# ComeNCap3.net
KiCad netlist of a schematic drawn in EAGLE
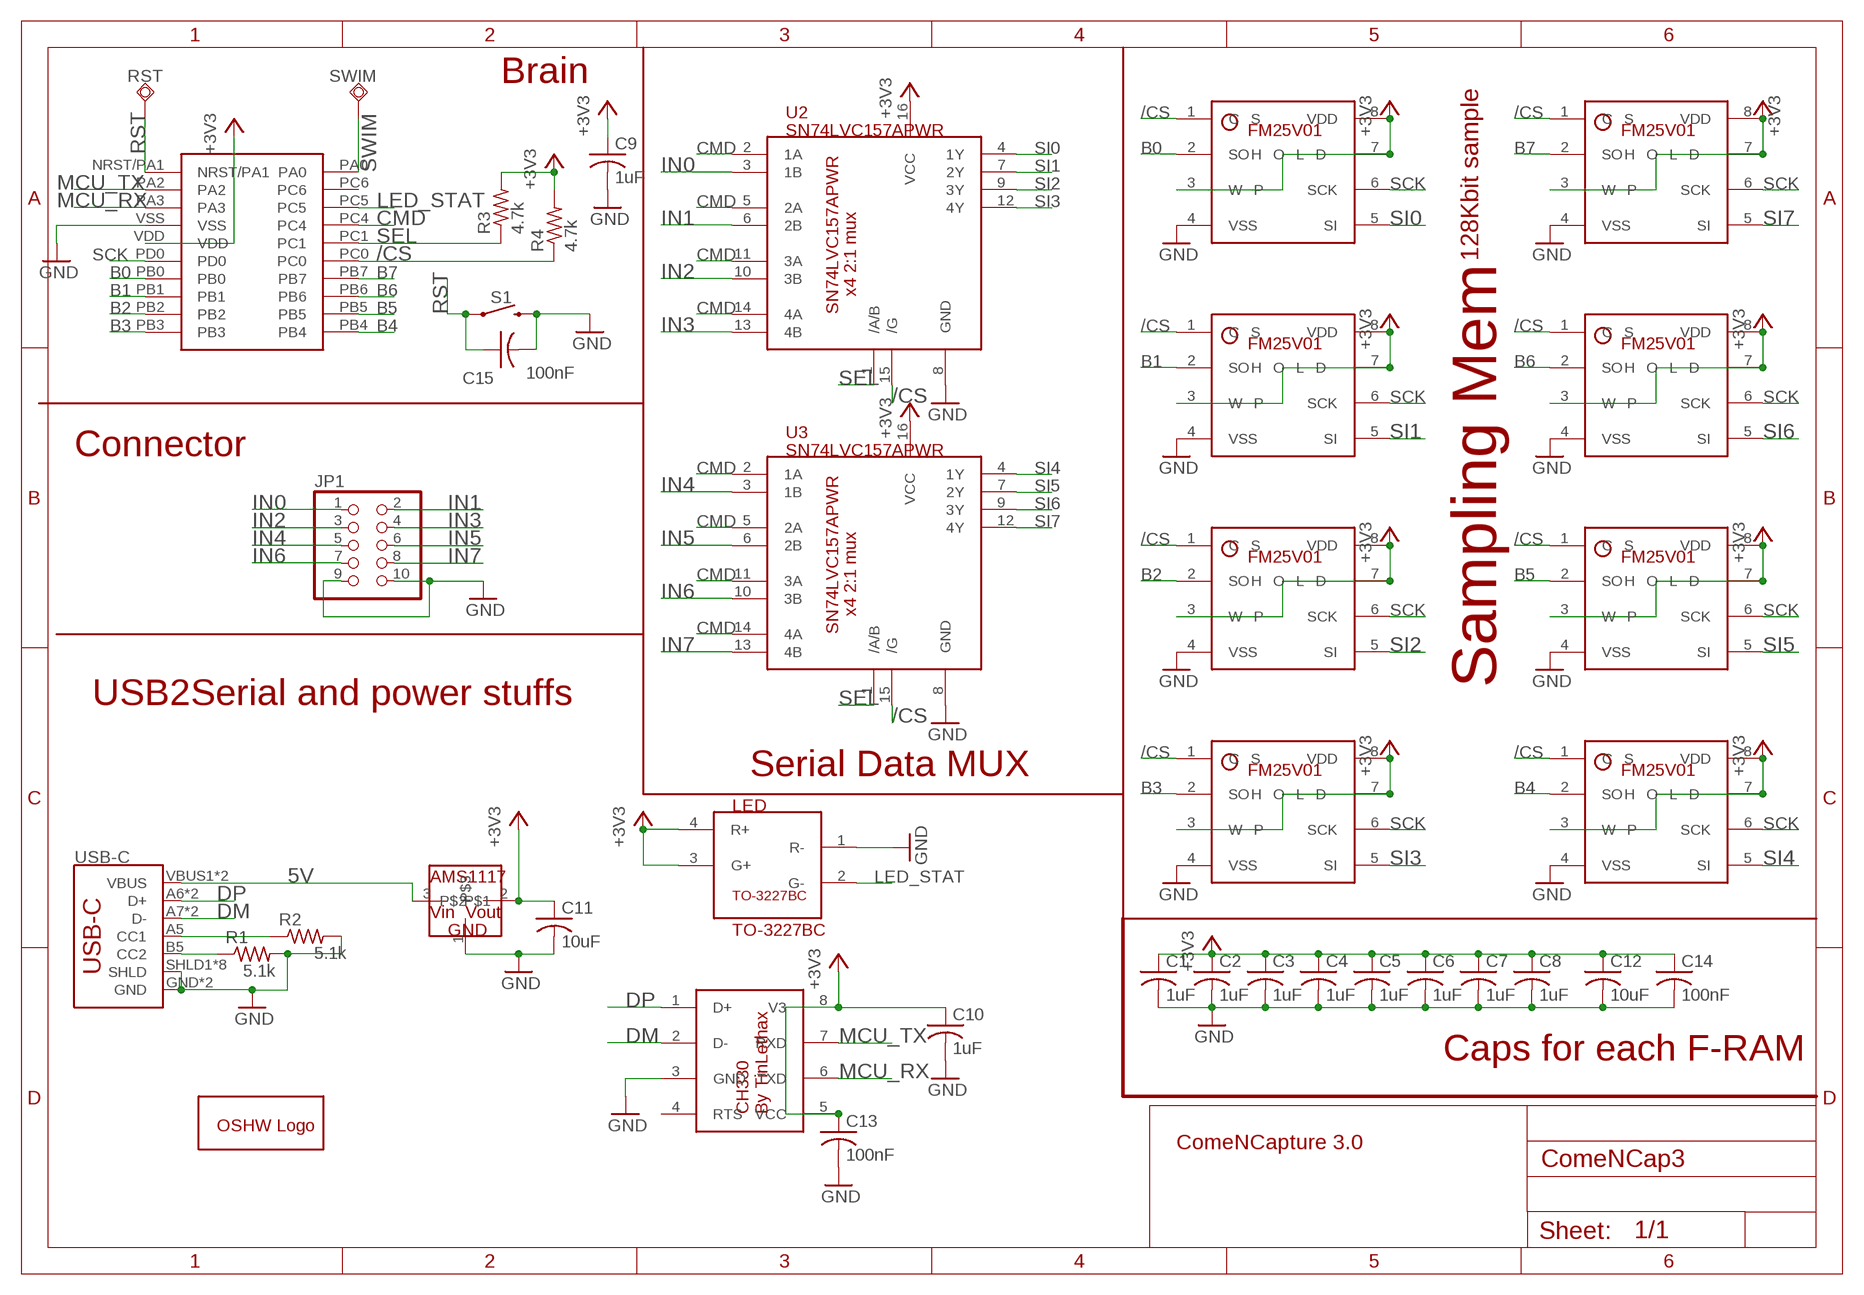
[diagram p0: schematic, sheet 1]

(export (version "E")
  (design (tool "Eeschema 10.0.6"))
  (components
    (comp (ref "C1")
      (value "1uF")
      (footprint "eagle-import:C0603")
      (libsource (lib "eagle-import") (part "C-USC0603"))
    )
    (comp (ref "C2")
      (value "1uF")
      (footprint "eagle-import:C0603")
      (libsource (lib "eagle-import") (part "C-USC0603"))
    )
    (comp (ref "C3")
      (value "1uF")
      (footprint "eagle-import:C0603")
      (libsource (lib "eagle-import") (part "C-USC0603"))
    )
    (comp (ref "C4")
      (value "1uF")
      (footprint "eagle-import:C0603")
      (libsource (lib "eagle-import") (part "C-USC0603"))
    )
    (comp (ref "C5")
      (value "1uF")
      (footprint "eagle-import:C0603")
      (libsource (lib "eagle-import") (part "C-USC0603"))
    )
    (comp (ref "C6")
      (value "1uF")
      (footprint "eagle-import:C0603")
      (libsource (lib "eagle-import") (part "C-USC0603"))
    )
    (comp (ref "C7")
      (value "1uF")
      (footprint "eagle-import:C0603")
      (libsource (lib "eagle-import") (part "C-USC0603"))
    )
    (comp (ref "C8")
      (value "1uF")
      (footprint "eagle-import:C0603")
      (libsource (lib "eagle-import") (part "C-USC0603"))
    )
    (comp (ref "C9")
      (value "1uF")
      (footprint "eagle-import:C0603")
      (libsource (lib "eagle-import") (part "C-USC0603"))
    )
    (comp (ref "C10")
      (value "1uF")
      (footprint "eagle-import:C0603")
      (libsource (lib "eagle-import") (part "C-USC0603"))
    )
    (comp (ref "C11")
      (value "10uF")
      (footprint "eagle-import:C0805")
      (libsource (lib "eagle-import") (part "C-USC0805"))
    )
    (comp (ref "C12")
      (value "10uF")
      (footprint "eagle-import:C0805")
      (libsource (lib "eagle-import") (part "C-USC0805"))
    )
    (comp (ref "C13")
      (value "100nF")
      (footprint "eagle-import:C1206")
      (libsource (lib "eagle-import") (part "C-USC1206"))
    )
    (comp (ref "C14")
      (value "100nF")
      (footprint "eagle-import:C1206")
      (libsource (lib "eagle-import") (part "C-USC1206"))
    )
    (comp (ref "C15")
      (value "100nF")
      (footprint "eagle-import:C1206")
      (libsource (lib "eagle-import") (part "C-USC1206"))
    )
    (comp (ref "GOLD_ORB_SM1")
      (value "OSHWLOGOLOGO5MM")
      (footprint "eagle-import:OSHW_5MM")
      (libsource (lib "eagle-import") (part "OSHWLOGOLOGO5MM"))
    )
    (comp (ref "JP1")
      (value "PINHD-2X5")
      (footprint "eagle-import:2X05")
      (libsource (lib "eagle-import") (part "PINHD-2X5"))
    )
    (comp (ref "LED")
      (value "TO-3227BC")
      (footprint "eagle-import:DIODFN320X270X40-4L")
      (libsource (lib "eagle-import") (part "TO-3227BC"))
    )
    (comp (ref "M0")
      (value "FM25V01")
      (footprint "eagle-import:SOIC127P601X172-8N")
      (fields (field (name "PARTNO") "FM52V01"))
      (libsource (lib "eagle-import") (part "FM25V01"))
    )
    (comp (ref "M1")
      (value "FM25V01")
      (footprint "eagle-import:SOIC127P601X172-8N")
      (fields (field (name "PARTNO") "FM52V01"))
      (libsource (lib "eagle-import") (part "FM25V01"))
    )
    (comp (ref "M2")
      (value "FM25V01")
      (footprint "eagle-import:SOIC127P601X172-8N")
      (fields (field (name "PARTNO") "FM52V01"))
      (libsource (lib "eagle-import") (part "FM25V01"))
    )
    (comp (ref "M3")
      (value "FM25V01")
      (footprint "eagle-import:SOIC127P601X172-8N")
      (fields (field (name "PARTNO") "FM52V01"))
      (libsource (lib "eagle-import") (part "FM25V01"))
    )
    (comp (ref "M4")
      (value "FM25V01")
      (footprint "eagle-import:SOIC127P601X172-8N")
      (fields (field (name "PARTNO") "FM52V01"))
      (libsource (lib "eagle-import") (part "FM25V01"))
    )
    (comp (ref "M5")
      (value "FM25V01")
      (footprint "eagle-import:SOIC127P601X172-8N")
      (fields (field (name "PARTNO") "FM52V01"))
      (libsource (lib "eagle-import") (part "FM25V01"))
    )
    (comp (ref "M6")
      (value "FM25V01")
      (footprint "eagle-import:SOIC127P601X172-8N")
      (fields (field (name "PARTNO") "FM52V01"))
      (libsource (lib "eagle-import") (part "FM25V01"))
    )
    (comp (ref "M7")
      (value "FM25V01")
      (footprint "eagle-import:SOIC127P601X172-8N")
      (fields (field (name "PARTNO") "FM52V01"))
      (libsource (lib "eagle-import") (part "FM25V01"))
    )
    (comp (ref "R1")
      (value "5.1k")
      (footprint "eagle-import:R0603")
      (libsource (lib "eagle-import") (part "R-US_R0603"))
    )
    (comp (ref "R2")
      (value "5.1k")
      (footprint "eagle-import:R0603")
      (libsource (lib "eagle-import") (part "R-US_R0603"))
    )
    (comp (ref "R3")
      (value "4.7k")
      (footprint "eagle-import:R0603")
      (libsource (lib "eagle-import") (part "R-US_R0603"))
    )
    (comp (ref "R4")
      (value "4.7k")
      (footprint "eagle-import:R0603")
      (libsource (lib "eagle-import") (part "R-US_R0603"))
    )
    (comp (ref "RST")
      (value "TPSQTP20R")
      (footprint "eagle-import:TP20R")
      (libsource (lib "eagle-import") (part "TPSQTP20R"))
    )
    (comp (ref "S1")
      (value "MOMENTARY-SWITCH-SPST-SMD-5.2-REDUNDANT")
      (footprint "eagle-import:TACTILE_SWITCH_SMD_5.2MM")
      (libsource (lib "eagle-import") (part "MOMENTARY-SWITCH-SPST-SMD-5.2-REDUNDANT"))
    )
    (comp (ref "SWIM")
      (value "TPSQTP20R")
      (footprint "eagle-import:TP20R")
      (libsource (lib "eagle-import") (part "TPSQTP20R"))
    )
    (comp (ref "U1")
      (value "STM8L151F3")
      (footprint "eagle-import:UFQFPN-20")
      (libsource (lib "eagle-import") (part "STM8L151F3"))
    )
    (comp (ref "U2")
      (value "SN74LVC157APWR")
      (footprint "eagle-import:SOP65P640X120-16L")
      (libsource (lib "eagle-import") (part "SN74LVC157APWR"))
    )
    (comp (ref "U3")
      (value "SN74LVC157APWR")
      (footprint "eagle-import:SOP65P640X120-16L")
      (libsource (lib "eagle-import") (part "SN74LVC157APWR"))
    )
    (comp (ref "U4")
      (value "CH330")
      (footprint "eagle-import:SOIC127P600X150-8N")
      (libsource (lib "eagle-import") (part "CH330"))
    )
    (comp (ref "U5")
      (value "AMS1117")
      (footprint "eagle-import:SOT223")
      (libsource (lib "eagle-import") (part "AMS1117"))
    )
    (comp (ref "USB-C")
      (value "USB_C16PIN")
      (footprint "eagle-import:USB-C-16P")
      (libsource (lib "eagle-import") (part "USB_C16PIN"))
    )
  )
  (nets
    (net (code "1") (name "+3V3") (class "Default")
      (node (ref "C1") (pin "1") (pinfunction "1_1") (pintype "passive"))
      (node (ref "C10") (pin "1") (pinfunction "1_1") (pintype "passive"))
      (node (ref "C11") (pin "1") (pinfunction "1_1") (pintype "passive"))
      (node (ref "C12") (pin "1") (pinfunction "1_1") (pintype "passive"))
      (node (ref "C13") (pin "1") (pinfunction "1_1") (pintype "passive"))
      (node (ref "C14") (pin "1") (pinfunction "1_1") (pintype "passive"))
      (node (ref "C2") (pin "1") (pinfunction "1_1") (pintype "passive"))
      (node (ref "C3") (pin "1") (pinfunction "1_1") (pintype "passive"))
      (node (ref "C4") (pin "1") (pinfunction "1_1") (pintype "passive"))
      (node (ref "C5") (pin "1") (pinfunction "1_1") (pintype "passive"))
      (node (ref "C6") (pin "1") (pinfunction "1_1") (pintype "passive"))
      (node (ref "C7") (pin "1") (pinfunction "1_1") (pintype "passive"))
      (node (ref "C8") (pin "1") (pinfunction "1_1") (pintype "passive"))
      (node (ref "C9") (pin "1") (pinfunction "1_1") (pintype "passive"))
      (node (ref "LED") (pin "3") (pinfunction "G+_3") (pintype "bidirectional"))
      (node (ref "LED") (pin "4") (pinfunction "R+_4") (pintype "bidirectional"))
      (node (ref "M0") (pin "3") (pinfunction "W̅P̅_3") (pintype "bidirectional"))
      (node (ref "M0") (pin "7") (pinfunction "H̅O̅L̅D̅_7") (pintype "bidirectional"))
      (node (ref "M0") (pin "8") (pinfunction "VDD_8") (pintype "bidirectional"))
      (node (ref "M1") (pin "3") (pinfunction "W̅P̅_3") (pintype "bidirectional"))
      (node (ref "M1") (pin "7") (pinfunction "H̅O̅L̅D̅_7") (pintype "bidirectional"))
      (node (ref "M1") (pin "8") (pinfunction "VDD_8") (pintype "bidirectional"))
      (node (ref "M2") (pin "3") (pinfunction "W̅P̅_3") (pintype "bidirectional"))
      (node (ref "M2") (pin "7") (pinfunction "H̅O̅L̅D̅_7") (pintype "bidirectional"))
      (node (ref "M2") (pin "8") (pinfunction "VDD_8") (pintype "bidirectional"))
      (node (ref "M3") (pin "3") (pinfunction "W̅P̅_3") (pintype "bidirectional"))
      (node (ref "M3") (pin "7") (pinfunction "H̅O̅L̅D̅_7") (pintype "bidirectional"))
      (node (ref "M3") (pin "8") (pinfunction "VDD_8") (pintype "bidirectional"))
      (node (ref "M4") (pin "3") (pinfunction "W̅P̅_3") (pintype "bidirectional"))
      (node (ref "M4") (pin "7") (pinfunction "H̅O̅L̅D̅_7") (pintype "bidirectional"))
      (node (ref "M4") (pin "8") (pinfunction "VDD_8") (pintype "bidirectional"))
      (node (ref "M5") (pin "3") (pinfunction "W̅P̅_3") (pintype "bidirectional"))
      (node (ref "M5") (pin "7") (pinfunction "H̅O̅L̅D̅_7") (pintype "bidirectional"))
      (node (ref "M5") (pin "8") (pinfunction "VDD_8") (pintype "bidirectional"))
      (node (ref "M6") (pin "3") (pinfunction "W̅P̅_3") (pintype "bidirectional"))
      (node (ref "M6") (pin "7") (pinfunction "H̅O̅L̅D̅_7") (pintype "bidirectional"))
      (node (ref "M6") (pin "8") (pinfunction "VDD_8") (pintype "bidirectional"))
      (node (ref "M7") (pin "3") (pinfunction "W̅P̅_3") (pintype "bidirectional"))
      (node (ref "M7") (pin "7") (pinfunction "H̅O̅L̅D̅_7") (pintype "bidirectional"))
      (node (ref "M7") (pin "8") (pinfunction "VDD_8") (pintype "bidirectional"))
      (node (ref "R3") (pin "2") (pinfunction "2_2") (pintype "passive"))
      (node (ref "R4") (pin "2") (pinfunction "2_2") (pintype "passive"))
      (node (ref "U1") (pin "VDD") (pinfunction "VDD_VDD") (pintype "bidirectional"))
      (node (ref "U2") (pin "16") (pinfunction "VCC_16") (pintype "bidirectional"))
      (node (ref "U3") (pin "16") (pinfunction "VCC_16") (pintype "bidirectional"))
      (node (ref "U4") (pin "5") (pinfunction "VCC_5") (pintype "bidirectional"))
      (node (ref "U4") (pin "8") (pinfunction "V3_8") (pintype "bidirectional"))
      (node (ref "U5") (pin "2") (pinfunction "P$2_2") (pintype "bidirectional"))
    )
    (net (code "2") (name "/5V") (class "Default")
      (node (ref "U5") (pin "3") (pinfunction "P$1_3") (pintype "bidirectional"))
      (node (ref "USB-C") (pin "VBUS1") (pinfunction "VBUS_VBUS1") (pintype "bidirectional"))
      (node (ref "USB-C") (pin "VBUS2") (pinfunction "VBUS_VBUS2") (pintype "bidirectional"))
    )
    (net (code "3") (name "/B0") (class "Default")
      (node (ref "M0") (pin "2") (pinfunction "SO_2") (pintype "bidirectional"))
      (node (ref "U1") (pin "PB0") (pinfunction "PB0_PB0") (pintype "bidirectional"))
    )
    (net (code "4") (name "/B1") (class "Default")
      (node (ref "M1") (pin "2") (pinfunction "SO_2") (pintype "bidirectional"))
      (node (ref "U1") (pin "PB1") (pinfunction "PB1_PB1") (pintype "bidirectional"))
    )
    (net (code "5") (name "/B2") (class "Default")
      (node (ref "M2") (pin "2") (pinfunction "SO_2") (pintype "bidirectional"))
      (node (ref "U1") (pin "PB2") (pinfunction "PB2_PB2") (pintype "bidirectional"))
    )
    (net (code "6") (name "/B3") (class "Default")
      (node (ref "M3") (pin "2") (pinfunction "SO_2") (pintype "bidirectional"))
      (node (ref "U1") (pin "PB3") (pinfunction "PB3_PB3") (pintype "bidirectional"))
    )
    (net (code "7") (name "/B4") (class "Default")
      (node (ref "M4") (pin "2") (pinfunction "SO_2") (pintype "bidirectional"))
      (node (ref "U1") (pin "PB4") (pinfunction "PB4_PB4") (pintype "bidirectional"))
    )
    (net (code "8") (name "/B5") (class "Default")
      (node (ref "M5") (pin "2") (pinfunction "SO_2") (pintype "bidirectional"))
      (node (ref "U1") (pin "PB5") (pinfunction "PB5_PB5") (pintype "bidirectional"))
    )
    (net (code "9") (name "/B6") (class "Default")
      (node (ref "M6") (pin "2") (pinfunction "SO_2") (pintype "bidirectional"))
      (node (ref "U1") (pin "PB6") (pinfunction "PB6_PB6") (pintype "bidirectional"))
    )
    (net (code "10") (name "/B7") (class "Default")
      (node (ref "M7") (pin "2") (pinfunction "SO_2") (pintype "bidirectional"))
      (node (ref "U1") (pin "PB7") (pinfunction "PB7_PB7") (pintype "bidirectional"))
    )
    (net (code "11") (name "/CMD") (class "Default")
      (node (ref "U1") (pin "PC4") (pinfunction "PC4_PC4") (pintype "bidirectional"))
      (node (ref "U2") (pin "11") (pinfunction "3A_11") (pintype "bidirectional"))
      (node (ref "U2") (pin "14") (pinfunction "4A_14") (pintype "bidirectional"))
      (node (ref "U2") (pin "2") (pinfunction "1A_2") (pintype "bidirectional"))
      (node (ref "U2") (pin "5") (pinfunction "2A_5") (pintype "bidirectional"))
      (node (ref "U3") (pin "11") (pinfunction "3A_11") (pintype "bidirectional"))
      (node (ref "U3") (pin "14") (pinfunction "4A_14") (pintype "bidirectional"))
      (node (ref "U3") (pin "2") (pinfunction "1A_2") (pintype "bidirectional"))
      (node (ref "U3") (pin "5") (pinfunction "2A_5") (pintype "bidirectional"))
    )
    (net (code "12") (name "/DM") (class "Default")
      (node (ref "U4") (pin "2") (pinfunction "D-_2") (pintype "bidirectional"))
      (node (ref "USB-C") (pin "A7") (pinfunction "D-_A7") (pintype "bidirectional"))
      (node (ref "USB-C") (pin "B7") (pinfunction "D-_B7") (pintype "bidirectional"))
    )
    (net (code "13") (name "/DP") (class "Default")
      (node (ref "U4") (pin "1") (pinfunction "D+_1") (pintype "bidirectional"))
      (node (ref "USB-C") (pin "A6") (pinfunction "D+_A6") (pintype "bidirectional"))
      (node (ref "USB-C") (pin "B6") (pinfunction "D+_B6") (pintype "bidirectional"))
    )
    (net (code "14") (name "/IN0") (class "Default")
      (node (ref "JP1") (pin "1") (pinfunction "1_1") (pintype "passive"))
      (node (ref "U2") (pin "3") (pinfunction "1B_3") (pintype "bidirectional"))
    )
    (net (code "15") (name "/IN1") (class "Default")
      (node (ref "JP1") (pin "2") (pinfunction "2_2") (pintype "passive"))
      (node (ref "U2") (pin "6") (pinfunction "2B_6") (pintype "bidirectional"))
    )
    (net (code "16") (name "/IN2") (class "Default")
      (node (ref "JP1") (pin "3") (pinfunction "3_3") (pintype "passive"))
      (node (ref "U2") (pin "10") (pinfunction "3B_10") (pintype "bidirectional"))
    )
    (net (code "17") (name "/IN3") (class "Default")
      (node (ref "JP1") (pin "4") (pinfunction "4_4") (pintype "passive"))
      (node (ref "U2") (pin "13") (pinfunction "4B_13") (pintype "bidirectional"))
    )
    (net (code "18") (name "/IN4") (class "Default")
      (node (ref "JP1") (pin "5") (pinfunction "5_5") (pintype "passive"))
      (node (ref "U3") (pin "3") (pinfunction "1B_3") (pintype "bidirectional"))
    )
    (net (code "19") (name "/IN5") (class "Default")
      (node (ref "JP1") (pin "6") (pinfunction "6_6") (pintype "passive"))
      (node (ref "U3") (pin "6") (pinfunction "2B_6") (pintype "bidirectional"))
    )
    (net (code "20") (name "/IN6") (class "Default")
      (node (ref "JP1") (pin "7") (pinfunction "7_7") (pintype "passive"))
      (node (ref "U3") (pin "10") (pinfunction "3B_10") (pintype "bidirectional"))
    )
    (net (code "21") (name "/IN7") (class "Default")
      (node (ref "JP1") (pin "8") (pinfunction "8_8") (pintype "passive"))
      (node (ref "U3") (pin "13") (pinfunction "4B_13") (pintype "bidirectional"))
    )
    (net (code "22") (name "/LED_STAT") (class "Default")
      (node (ref "LED") (pin "2") (pinfunction "G-_2") (pintype "bidirectional"))
      (node (ref "U1") (pin "PC5") (pinfunction "PC5_PC5") (pintype "bidirectional"))
    )
    (net (code "23") (name "/MCU_RX") (class "Default")
      (node (ref "U1") (pin "PA3") (pinfunction "PA3_PA3") (pintype "bidirectional"))
      (node (ref "U4") (pin "6") (pinfunction "TXD_6") (pintype "bidirectional"))
    )
    (net (code "24") (name "/MCU_TX") (class "Default")
      (node (ref "U1") (pin "PA2") (pinfunction "PA2_PA2") (pintype "bidirectional"))
      (node (ref "U4") (pin "7") (pinfunction "RXD_7") (pintype "bidirectional"))
    )
    (net (code "25") (name "/RST") (class "Default")
      (node (ref "C15") (pin "1") (pinfunction "1_1") (pintype "passive"))
      (node (ref "RST") (pin "TP") (pinfunction "TP_TP") (pintype "input"))
      (node (ref "S1") (pin "1") (pinfunction "1_1") (pintype "passive"))
      (node (ref "S1") (pin "2") (pinfunction "1_2") (pintype "passive"))
      (node (ref "U1") (pin "NRST/PA1") (pinfunction "NRST/PA1_NRST/PA1") (pintype "bidirectional"))
    )
    (net (code "26") (name "/SCK") (class "Default")
      (node (ref "M0") (pin "6") (pinfunction "SCK_6") (pintype "bidirectional"))
      (node (ref "M1") (pin "6") (pinfunction "SCK_6") (pintype "bidirectional"))
      (node (ref "M2") (pin "6") (pinfunction "SCK_6") (pintype "bidirectional"))
      (node (ref "M3") (pin "6") (pinfunction "SCK_6") (pintype "bidirectional"))
      (node (ref "M4") (pin "6") (pinfunction "SCK_6") (pintype "bidirectional"))
      (node (ref "M5") (pin "6") (pinfunction "SCK_6") (pintype "bidirectional"))
      (node (ref "M6") (pin "6") (pinfunction "SCK_6") (pintype "bidirectional"))
      (node (ref "M7") (pin "6") (pinfunction "SCK_6") (pintype "bidirectional"))
      (node (ref "U1") (pin "PD0") (pinfunction "PD0_PD0") (pintype "bidirectional"))
    )
    (net (code "27") (name "/SEL") (class "Default")
      (node (ref "R3") (pin "1") (pinfunction "1_1") (pintype "passive"))
      (node (ref "U1") (pin "PC1") (pinfunction "PC1_PC1") (pintype "bidirectional"))
      (node (ref "U2") (pin "1") (pinfunction "/A/B_1") (pintype "bidirectional"))
      (node (ref "U3") (pin "1") (pinfunction "/A/B_1") (pintype "bidirectional"))
    )
    (net (code "28") (name "/SI0") (class "Default")
      (node (ref "M0") (pin "5") (pinfunction "SI_5") (pintype "bidirectional"))
      (node (ref "U2") (pin "4") (pinfunction "1Y_4") (pintype "bidirectional"))
    )
    (net (code "29") (name "/SI1") (class "Default")
      (node (ref "M1") (pin "5") (pinfunction "SI_5") (pintype "bidirectional"))
      (node (ref "U2") (pin "7") (pinfunction "2Y_7") (pintype "bidirectional"))
    )
    (net (code "30") (name "/SI2") (class "Default")
      (node (ref "M2") (pin "5") (pinfunction "SI_5") (pintype "bidirectional"))
      (node (ref "U2") (pin "9") (pinfunction "3Y_9") (pintype "bidirectional"))
    )
    (net (code "31") (name "/SI3") (class "Default")
      (node (ref "M3") (pin "5") (pinfunction "SI_5") (pintype "bidirectional"))
      (node (ref "U2") (pin "12") (pinfunction "4Y_12") (pintype "bidirectional"))
    )
    (net (code "32") (name "/SI4") (class "Default")
      (node (ref "M4") (pin "5") (pinfunction "SI_5") (pintype "bidirectional"))
      (node (ref "U3") (pin "4") (pinfunction "1Y_4") (pintype "bidirectional"))
    )
    (net (code "33") (name "/SI5") (class "Default")
      (node (ref "M5") (pin "5") (pinfunction "SI_5") (pintype "bidirectional"))
      (node (ref "U3") (pin "7") (pinfunction "2Y_7") (pintype "bidirectional"))
    )
    (net (code "34") (name "/SI6") (class "Default")
      (node (ref "M6") (pin "5") (pinfunction "SI_5") (pintype "bidirectional"))
      (node (ref "U3") (pin "9") (pinfunction "3Y_9") (pintype "bidirectional"))
    )
    (net (code "35") (name "/SI7") (class "Default")
      (node (ref "M7") (pin "5") (pinfunction "SI_5") (pintype "bidirectional"))
      (node (ref "U3") (pin "12") (pinfunction "4Y_12") (pintype "bidirectional"))
    )
    (net (code "36") (name "/SWIM") (class "Default")
      (node (ref "SWIM") (pin "TP") (pinfunction "TP_TP") (pintype "input"))
      (node (ref "U1") (pin "PA0") (pinfunction "PA0_PA0") (pintype "bidirectional"))
    )
    (net (code "37") (name "/{slash}CS") (class "Default")
      (node (ref "M0") (pin "1") (pinfunction "C̅S̅_1") (pintype "bidirectional"))
      (node (ref "M1") (pin "1") (pinfunction "C̅S̅_1") (pintype "bidirectional"))
      (node (ref "M2") (pin "1") (pinfunction "C̅S̅_1") (pintype "bidirectional"))
      (node (ref "M3") (pin "1") (pinfunction "C̅S̅_1") (pintype "bidirectional"))
      (node (ref "M4") (pin "1") (pinfunction "C̅S̅_1") (pintype "bidirectional"))
      (node (ref "M5") (pin "1") (pinfunction "C̅S̅_1") (pintype "bidirectional"))
      (node (ref "M6") (pin "1") (pinfunction "C̅S̅_1") (pintype "bidirectional"))
      (node (ref "M7") (pin "1") (pinfunction "C̅S̅_1") (pintype "bidirectional"))
      (node (ref "R4") (pin "1") (pinfunction "1_1") (pintype "passive"))
      (node (ref "U1") (pin "PC0") (pinfunction "PC0_PC0") (pintype "bidirectional"))
      (node (ref "U2") (pin "15") (pinfunction "/G_15") (pintype "bidirectional"))
      (node (ref "U3") (pin "15") (pinfunction "/G_15") (pintype "bidirectional"))
    )
    (net (code "38") (name "GND") (class "Default")
      (node (ref "C1") (pin "2") (pinfunction "2_2") (pintype "passive"))
      (node (ref "C10") (pin "2") (pinfunction "2_2") (pintype "passive"))
      (node (ref "C11") (pin "2") (pinfunction "2_2") (pintype "passive"))
      (node (ref "C12") (pin "2") (pinfunction "2_2") (pintype "passive"))
      (node (ref "C13") (pin "2") (pinfunction "2_2") (pintype "passive"))
      (node (ref "C14") (pin "2") (pinfunction "2_2") (pintype "passive"))
      (node (ref "C15") (pin "2") (pinfunction "2_2") (pintype "passive"))
      (node (ref "C2") (pin "2") (pinfunction "2_2") (pintype "passive"))
      (node (ref "C3") (pin "2") (pinfunction "2_2") (pintype "passive"))
      (node (ref "C4") (pin "2") (pinfunction "2_2") (pintype "passive"))
      (node (ref "C5") (pin "2") (pinfunction "2_2") (pintype "passive"))
      (node (ref "C6") (pin "2") (pinfunction "2_2") (pintype "passive"))
      (node (ref "C7") (pin "2") (pinfunction "2_2") (pintype "passive"))
      (node (ref "C8") (pin "2") (pinfunction "2_2") (pintype "passive"))
      (node (ref "C9") (pin "2") (pinfunction "2_2") (pintype "passive"))
      (node (ref "JP1") (pin "10") (pinfunction "10_10") (pintype "passive"))
      (node (ref "JP1") (pin "9") (pinfunction "9_9") (pintype "passive"))
      (node (ref "LED") (pin "1") (pinfunction "R-_1") (pintype "bidirectional"))
      (node (ref "M0") (pin "4") (pinfunction "VSS_4") (pintype "bidirectional"))
      (node (ref "M1") (pin "4") (pinfunction "VSS_4") (pintype "bidirectional"))
      (node (ref "M2") (pin "4") (pinfunction "VSS_4") (pintype "bidirectional"))
      (node (ref "M3") (pin "4") (pinfunction "VSS_4") (pintype "bidirectional"))
      (node (ref "M4") (pin "4") (pinfunction "VSS_4") (pintype "bidirectional"))
      (node (ref "M5") (pin "4") (pinfunction "VSS_4") (pintype "bidirectional"))
      (node (ref "M6") (pin "4") (pinfunction "VSS_4") (pintype "bidirectional"))
      (node (ref "M7") (pin "4") (pinfunction "VSS_4") (pintype "bidirectional"))
      (node (ref "R1") (pin "2") (pinfunction "2_2") (pintype "passive"))
      (node (ref "R2") (pin "2") (pinfunction "2_2") (pintype "passive"))
      (node (ref "S1") (pin "3") (pinfunction "2_3") (pintype "passive"))
      (node (ref "S1") (pin "4") (pinfunction "2_4") (pintype "passive"))
      (node (ref "U1") (pin "VSS") (pinfunction "VSS_VSS") (pintype "bidirectional"))
      (node (ref "U2") (pin "8") (pinfunction "GND_8") (pintype "bidirectional"))
      (node (ref "U3") (pin "8") (pinfunction "GND_8") (pintype "bidirectional"))
      (node (ref "U4") (pin "3") (pinfunction "GND_3") (pintype "bidirectional"))
      (node (ref "U5") (pin "1") (pinfunction "P$3_1") (pintype "bidirectional"))
      (node (ref "USB-C") (pin "GND") (pinfunction "GND_GND") (pintype "bidirectional"))
      (node (ref "USB-C") (pin "GND2") (pinfunction "GND_GND2") (pintype "bidirectional"))
      (node (ref "USB-C") (pin "SHLD1") (pinfunction "SHLD_SHLD1") (pintype "bidirectional"))
      (node (ref "USB-C") (pin "SHLD2") (pinfunction "SHLD_SHLD2") (pintype "bidirectional"))
      (node (ref "USB-C") (pin "SHLD3") (pinfunction "SHLD_SHLD3") (pintype "bidirectional"))
      (node (ref "USB-C") (pin "SHLD4") (pinfunction "SHLD_SHLD4") (pintype "bidirectional"))
      (node (ref "USB-C") (pin "SHLD5") (pinfunction "SHLD_SHLD5") (pintype "bidirectional"))
      (node (ref "USB-C") (pin "SHLD6") (pinfunction "SHLD_SHLD6") (pintype "bidirectional"))
      (node (ref "USB-C") (pin "SHLD7") (pinfunction "SHLD_SHLD7") (pintype "bidirectional"))
      (node (ref "USB-C") (pin "SHLD8") (pinfunction "SHLD_SHLD8") (pintype "bidirectional"))
    )
    (net (code "39") (name "Net-(USB-C-CC1)") (class "Default")
      (node (ref "R2") (pin "1") (pinfunction "1_1") (pintype "passive"))
      (node (ref "USB-C") (pin "A5") (pinfunction "CC1_A5") (pintype "bidirectional"))
    )
    (net (code "40") (name "Net-(USB-C-CC2)") (class "Default")
      (node (ref "R1") (pin "1") (pinfunction "1_1") (pintype "passive"))
      (node (ref "USB-C") (pin "B5") (pinfunction "CC2_B5") (pintype "bidirectional"))
    )
    (net (code "41") (name "unconnected-(U1-PadPC6)") (class "Default")
      (node (ref "U1") (pin "PC6") (pinfunction "PC6_PC6") (pintype "bidirectional"))
    )
    (net (code "42") (name "unconnected-(U4-RTS-Pad4)") (class "Default")
      (node (ref "U4") (pin "4") (pinfunction "RTS_4") (pintype "bidirectional"))
    )
  )
)
